# Trial_1_ECE411_Group_15_UPDATED_1.net
KiCad netlist of a schematic drawn in EAGLE
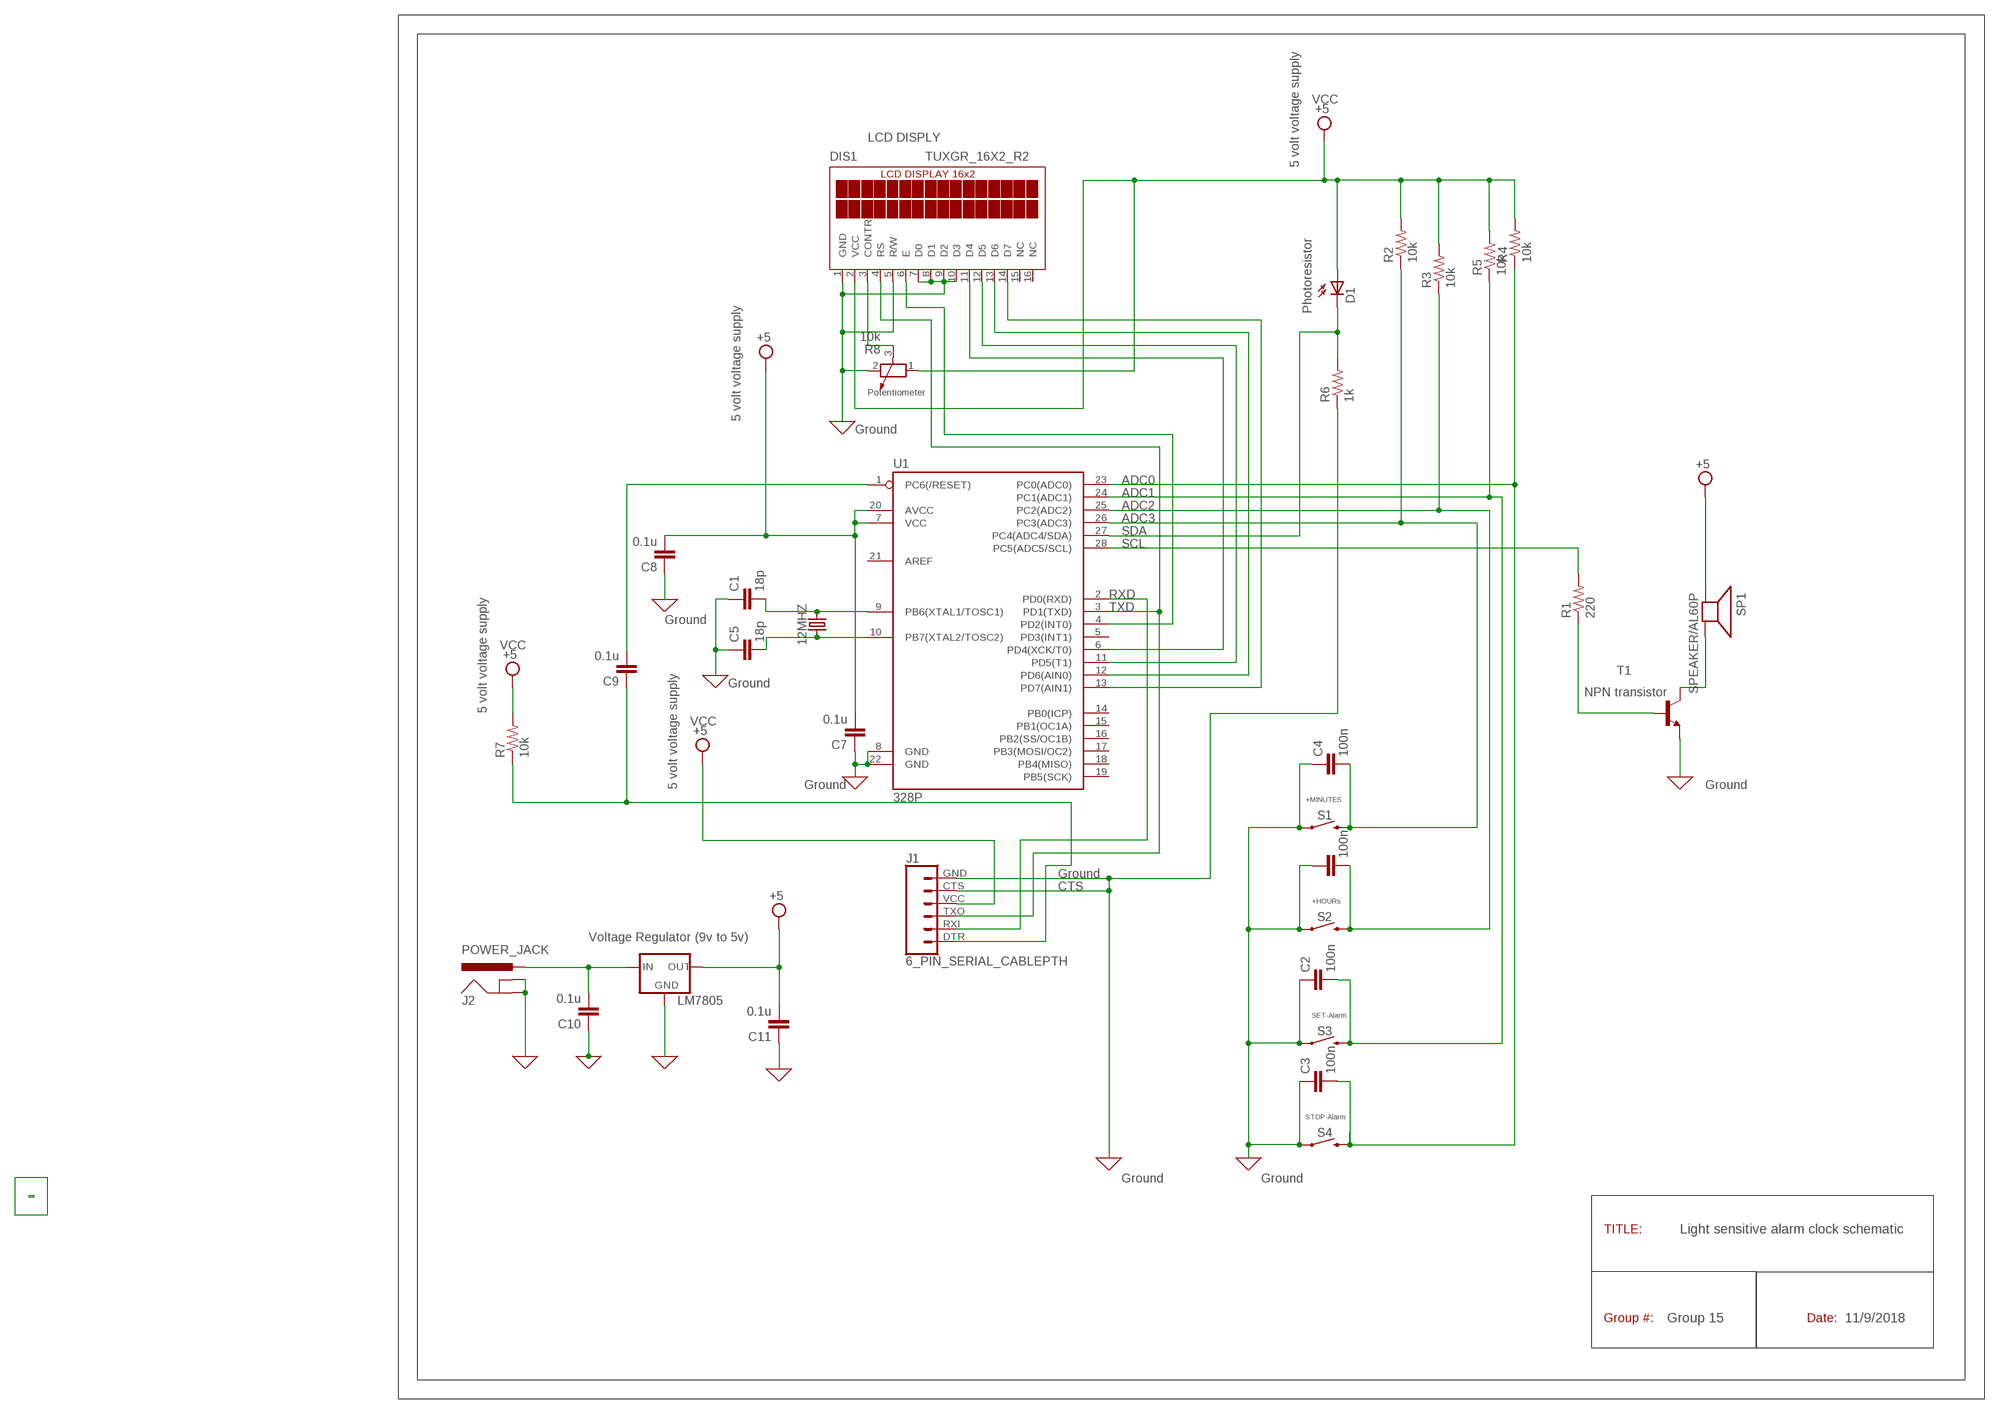
[diagram p0: schematic, sheet 1]

(export (version "E")
  (design (tool "Eeschema 10.0.6"))
  (components
    (comp (ref "12MHZ")
      (value "CRYSTALPTH-2X6")
      (footprint "eagle-import:CRYSTAL-PTH-2X6-CYL")
      (libsource (lib "eagle-import") (part "CRYSTALPTH-2X6"))
    )
    (comp (ref "C1")
      (value "18p")
      (footprint "eagle-import:C2.5-3")
      (libsource (lib "eagle-import") (part "C2,5-3"))
    )
    (comp (ref "C2")
      (value "100n")
      (footprint "eagle-import:C2.5-3")
      (libsource (lib "eagle-import") (part "C2,5-3"))
    )
    (comp (ref "C3")
      (value "100n")
      (footprint "eagle-import:C2.5-3")
      (libsource (lib "eagle-import") (part "C2,5-3"))
    )
    (comp (ref "C4")
      (value "100n")
      (footprint "eagle-import:C2.5-3")
      (libsource (lib "eagle-import") (part "C2,5-3"))
    )
    (comp (ref "C5")
      (value "18p")
      (footprint "eagle-import:C2.5-3")
      (libsource (lib "eagle-import") (part "C2,5-3"))
    )
    (comp (ref "C6")
      (value "100n")
      (footprint "eagle-import:C2.5-3")
      (libsource (lib "eagle-import") (part "C2,5-3"))
    )
    (comp (ref "C7")
      (value "0.1u")
      (footprint "eagle-import:C2.5-3")
      (libsource (lib "eagle-import") (part "C2,5-3"))
    )
    (comp (ref "C8")
      (value "0.1u")
      (footprint "eagle-import:C2.5-3")
      (libsource (lib "eagle-import") (part "C2,5-3"))
    )
    (comp (ref "C9")
      (value "0.1u")
      (footprint "eagle-import:C2.5-3")
      (libsource (lib "eagle-import") (part "C2,5-3"))
    )
    (comp (ref "C10")
      (value "0.1u")
      (footprint "eagle-import:C2.5-3")
      (libsource (lib "eagle-import") (part "C2,5-3"))
    )
    (comp (ref "C11")
      (value "0.1u")
      (footprint "eagle-import:C2.5-3")
      (libsource (lib "eagle-import") (part "C2,5-3"))
    )
    (comp (ref "D1")
      (value "BPW32")
      (footprint "eagle-import:BPW32")
      (libsource (lib "eagle-import") (part "BPW32"))
    )
    (comp (ref "DIS1")
      (value "TUXGR_16X2_R2")
      (footprint "eagle-import:TUXGR_16X2_R2")
      (libsource (lib "eagle-import") (part "TUXGR_16X2_R2"))
    )
    (comp (ref "J1")
      (value "6_PIN_SERIAL_CABLEPTH")
      (footprint "eagle-import:FTDI_BASIC")
      (libsource (lib "eagle-import") (part "6_PIN_SERIAL_CABLEPTH"))
    )
    (comp (ref "J2")
      (value "POWER_JACK")
      (footprint "eagle-import:POWER_JACK_PTH")
      (libsource (lib "eagle-import") (part "POWER_JACK"))
    )
    (comp (ref "LM7805")
      (value "R-78E5.0-1.0")
      (footprint "eagle-import:DC-DC_CONVERTER_78XX")
      (libsource (lib "eagle-import") (part "R-78E5.0-1.0"))
    )
    (comp (ref "R1")
      (value "220")
      (footprint "eagle-import:0204V")
      (libsource (lib "eagle-import") (part "R-US_0204/2V"))
    )
    (comp (ref "R2")
      (value "10k")
      (footprint "eagle-import:0204V")
      (libsource (lib "eagle-import") (part "R-US_0204/2V"))
    )
    (comp (ref "R3")
      (value "10k")
      (footprint "eagle-import:0204V")
      (libsource (lib "eagle-import") (part "R-US_0204/2V"))
    )
    (comp (ref "R4")
      (value "10k")
      (footprint "eagle-import:0204V")
      (libsource (lib "eagle-import") (part "R-US_0204/2V"))
    )
    (comp (ref "R5")
      (value "10k")
      (footprint "eagle-import:0204V")
      (libsource (lib "eagle-import") (part "R-US_0204/2V"))
    )
    (comp (ref "R6")
      (value "1k")
      (footprint "eagle-import:0204V")
      (libsource (lib "eagle-import") (part "R-US_0204/2V"))
    )
    (comp (ref "R7")
      (value "10k")
      (footprint "eagle-import:0204V")
      (libsource (lib "eagle-import") (part "R-US_0204/2V"))
    )
    (comp (ref "R8")
      (value "10k")
      (footprint "eagle-import:PT-10")
      (libsource (lib "eagle-import") (part "POTENTIOMETER_PT-10"))
    )
    (comp (ref "S1")
      (value "MOMENTARY-SWITCH-SPST-PTH-6.0MM")
      (footprint "eagle-import:TACTILE_SWITCH_PTH_6.0MM")
      (libsource (lib "eagle-import") (part "MOMENTARY-SWITCH-SPST-PTH-6.0MM"))
    )
    (comp (ref "S2")
      (value "MOMENTARY-SWITCH-SPST-PTH-6.0MM")
      (footprint "eagle-import:TACTILE_SWITCH_PTH_6.0MM")
      (libsource (lib "eagle-import") (part "MOMENTARY-SWITCH-SPST-PTH-6.0MM"))
    )
    (comp (ref "S3")
      (value "MOMENTARY-SWITCH-SPST-PTH-6.0MM")
      (footprint "eagle-import:TACTILE_SWITCH_PTH_6.0MM")
      (libsource (lib "eagle-import") (part "MOMENTARY-SWITCH-SPST-PTH-6.0MM"))
    )
    (comp (ref "S4")
      (value "MOMENTARY-SWITCH-SPST-PTH-6.0MM")
      (footprint "eagle-import:TACTILE_SWITCH_PTH_6.0MM")
      (libsource (lib "eagle-import") (part "MOMENTARY-SWITCH-SPST-PTH-6.0MM"))
    )
    (comp (ref "SP1")
      (value "SPEAKER/AL60P")
      (footprint "eagle-import:AL60P")
      (libsource (lib "eagle-import") (part "SPEAKER/AL60P"))
    )
    (comp (ref "T1")
      (value "2N2222")
      (footprint "eagle-import:TO92-EBC-OVAL")
      (libsource (lib "eagle-import") (part "2N2222"))
    )
    (comp (ref "U1")
      (value "328P")
      (footprint "eagle-import:DIP28")
      (libsource (lib "eagle-import") (part "ATMEGA328P_PDIP"))
    )
  )
  (nets
    (net (code "1") (name "+5") (class "Default")
      (node (ref "C11") (pin "2") (pinfunction "2_2") (pintype "passive"))
      (node (ref "C7") (pin "2") (pinfunction "2_2") (pintype "passive"))
      (node (ref "C8") (pin "2") (pinfunction "2_2") (pintype "passive"))
      (node (ref "D1") (pin "A") (pinfunction "A_A") (pintype "passive"))
      (node (ref "DIS1") (pin "2") (pinfunction "VCC_2") (pintype "power_in"))
      (node (ref "J1") (pin "VCC") (pinfunction "4_VCC") (pintype "passive"))
      (node (ref "LM7805") (pin "VOUT") (pinfunction "OUT_VOUT") (pintype "passive"))
      (node (ref "R2") (pin "2") (pinfunction "2_2") (pintype "passive"))
      (node (ref "R3") (pin "2") (pinfunction "2_2") (pintype "passive"))
      (node (ref "R4") (pin "2") (pinfunction "2_2") (pintype "passive"))
      (node (ref "R5") (pin "2") (pinfunction "2_2") (pintype "passive"))
      (node (ref "R7") (pin "2") (pinfunction "2_2") (pintype "passive"))
      (node (ref "R8") (pin "1") (pinfunction "1_1") (pintype "passive"))
      (node (ref "SP1") (pin "1") (pinfunction "+_1") (pintype "passive"))
      (node (ref "U1") (pin "20") (pinfunction "AVCC_20") (pintype "bidirectional"))
      (node (ref "U1") (pin "7") (pinfunction "VCC_7") (pintype "bidirectional"))
    )
    (net (code "2") (name "GND") (class "Default")
      (node (ref "C1") (pin "1") (pinfunction "1_1") (pintype "passive"))
      (node (ref "C10") (pin "1") (pinfunction "1_1") (pintype "passive"))
      (node (ref "C11") (pin "1") (pinfunction "1_1") (pintype "passive"))
      (node (ref "C2") (pin "1") (pinfunction "1_1") (pintype "passive"))
      (node (ref "C3") (pin "1") (pinfunction "1_1") (pintype "passive"))
      (node (ref "C4") (pin "1") (pinfunction "1_1") (pintype "passive"))
      (node (ref "C5") (pin "1") (pinfunction "1_1") (pintype "passive"))
      (node (ref "C6") (pin "1") (pinfunction "1_1") (pintype "passive"))
      (node (ref "C7") (pin "1") (pinfunction "1_1") (pintype "passive"))
      (node (ref "C8") (pin "1") (pinfunction "1_1") (pintype "passive"))
      (node (ref "DIS1") (pin "1") (pinfunction "GND_1") (pintype "power_in"))
      (node (ref "DIS1") (pin "10") (pinfunction "D3_10") (pintype "input"))
      (node (ref "DIS1") (pin "5") (pinfunction "R/W_5") (pintype "input"))
      (node (ref "DIS1") (pin "7") (pinfunction "D0_7") (pintype "input"))
      (node (ref "DIS1") (pin "8") (pinfunction "D1_8") (pintype "input"))
      (node (ref "DIS1") (pin "9") (pinfunction "D2_9") (pintype "input"))
      (node (ref "J1") (pin "CTS") (pinfunction "5_CTS") (pintype "passive"))
      (node (ref "J1") (pin "GND") (pinfunction "6_GND") (pintype "passive"))
      (node (ref "J2") (pin "GND") (pinfunction "GND_GND") (pintype "bidirectional"))
      (node (ref "J2") (pin "GNDBREAK") (pinfunction "GNDBREAK_GNDBREAK") (pintype "bidirectional"))
      (node (ref "LM7805") (pin "GND") (pinfunction "GND_GND") (pintype "input"))
      (node (ref "R6") (pin "1") (pinfunction "1_1") (pintype "passive"))
      (node (ref "R8") (pin "2") (pinfunction "2_2") (pintype "passive"))
      (node (ref "S1") (pin "1") (pinfunction "1_1") (pintype "passive"))
      (node (ref "S2") (pin "1") (pinfunction "1_1") (pintype "passive"))
      (node (ref "S3") (pin "1") (pinfunction "1_1") (pintype "passive"))
      (node (ref "S4") (pin "1") (pinfunction "1_1") (pintype "passive"))
      (node (ref "T1") (pin "E") (pinfunction "E_E") (pintype "passive"))
      (node (ref "U1") (pin "22") (pinfunction "GND_22") (pintype "bidirectional"))
      (node (ref "U1") (pin "8") (pinfunction "GND_8") (pintype "bidirectional"))
    )
    (net (code "3") (name "Net-(D1-C)") (class "Default")
      (node (ref "D1") (pin "K") (pinfunction "C_K") (pintype "passive"))
      (node (ref "R6") (pin "2") (pinfunction "2_2") (pintype "passive"))
      (node (ref "U1") (pin "27") (pinfunction "PC4(ADC4/SDA)_27") (pintype "bidirectional"))
    )
    (net (code "4") (name "Net-(DIS1-CONTR)") (class "Default")
      (node (ref "DIS1") (pin "3") (pinfunction "CONTR_3") (pintype "input"))
      (node (ref "R8") (pin "3") (pinfunction "3_3") (pintype "passive"))
    )
    (net (code "5") (name "Net-(DIS1-D4)") (class "Default")
      (node (ref "DIS1") (pin "11") (pinfunction "D4_11") (pintype "input"))
      (node (ref "U1") (pin "6") (pinfunction "PD4(XCK/T0)_6") (pintype "bidirectional"))
    )
    (net (code "6") (name "Net-(DIS1-D5)") (class "Default")
      (node (ref "DIS1") (pin "12") (pinfunction "D5_12") (pintype "input"))
      (node (ref "U1") (pin "11") (pinfunction "PD5(T1)_11") (pintype "bidirectional"))
    )
    (net (code "7") (name "Net-(DIS1-D6)") (class "Default")
      (node (ref "DIS1") (pin "13") (pinfunction "D6_13") (pintype "input"))
      (node (ref "U1") (pin "12") (pinfunction "PD6(AIN0)_12") (pintype "bidirectional"))
    )
    (net (code "8") (name "Net-(DIS1-D7)") (class "Default")
      (node (ref "DIS1") (pin "14") (pinfunction "D7_14") (pintype "input"))
      (node (ref "U1") (pin "13") (pinfunction "PD7(AIN1)_13") (pintype "bidirectional"))
    )
    (net (code "9") (name "Net-(DIS1-E)") (class "Default")
      (node (ref "DIS1") (pin "6") (pinfunction "E_6") (pintype "input"))
      (node (ref "U1") (pin "4") (pinfunction "PD2(INT0)_4") (pintype "bidirectional"))
    )
    (net (code "10") (name "Net-(DIS1-RS)") (class "Default")
      (node (ref "DIS1") (pin "4") (pinfunction "RS_4") (pintype "input"))
      (node (ref "J1") (pin "TXO") (pinfunction "3_TXO") (pintype "passive"))
      (node (ref "U1") (pin "3") (pinfunction "PD1(TXD)_3") (pintype "bidirectional"))
    )
    (net (code "11") (name "Net-(J1-1)") (class "Default")
      (node (ref "C9") (pin "1") (pinfunction "1_1") (pintype "passive"))
      (node (ref "J1") (pin "DTR") (pinfunction "1_DTR") (pintype "passive"))
      (node (ref "R7") (pin "1") (pinfunction "1_1") (pintype "passive"))
    )
    (net (code "12") (name "Net-(J1-2)") (class "Default")
      (node (ref "J1") (pin "RXI") (pinfunction "2_RXI") (pintype "passive"))
      (node (ref "U1") (pin "2") (pinfunction "PD0(RXD)_2") (pintype "bidirectional"))
    )
    (net (code "13") (name "Net-(LM7805-IN)") (class "Default")
      (node (ref "C10") (pin "2") (pinfunction "2_2") (pintype "passive"))
      (node (ref "J2") (pin "PWR") (pinfunction "PWR_PWR") (pintype "bidirectional"))
      (node (ref "LM7805") (pin "VIN") (pinfunction "IN_VIN") (pintype "input"))
    )
    (net (code "14") (name "Net-(R1-Pad1)") (class "Default")
      (node (ref "R1") (pin "1") (pinfunction "1_1") (pintype "passive"))
      (node (ref "T1") (pin "B") (pinfunction "B_B") (pintype "passive"))
    )
    (net (code "15") (name "Net-(S1-2)") (class "Default")
      (node (ref "C4") (pin "2") (pinfunction "2_2") (pintype "passive"))
      (node (ref "R2") (pin "1") (pinfunction "1_1") (pintype "passive"))
      (node (ref "S1") (pin "3") (pinfunction "2_3") (pintype "passive"))
      (node (ref "U1") (pin "26") (pinfunction "PC3(ADC3)_26") (pintype "bidirectional"))
    )
    (net (code "16") (name "Net-(S2-2)") (class "Default")
      (node (ref "C6") (pin "2") (pinfunction "2_2") (pintype "passive"))
      (node (ref "R3") (pin "1") (pinfunction "1_1") (pintype "passive"))
      (node (ref "S2") (pin "3") (pinfunction "2_3") (pintype "passive"))
      (node (ref "U1") (pin "25") (pinfunction "PC2(ADC2)_25") (pintype "bidirectional"))
    )
    (net (code "17") (name "Net-(S3-2)") (class "Default")
      (node (ref "C2") (pin "2") (pinfunction "2_2") (pintype "passive"))
      (node (ref "R5") (pin "1") (pinfunction "1_1") (pintype "passive"))
      (node (ref "S3") (pin "3") (pinfunction "2_3") (pintype "passive"))
      (node (ref "U1") (pin "24") (pinfunction "PC1(ADC1)_24") (pintype "bidirectional"))
    )
    (net (code "18") (name "Net-(S4-2)") (class "Default")
      (node (ref "C3") (pin "2") (pinfunction "2_2") (pintype "passive"))
      (node (ref "R4") (pin "1") (pinfunction "1_1") (pintype "passive"))
      (node (ref "S4") (pin "3") (pinfunction "2_3") (pintype "passive"))
      (node (ref "U1") (pin "23") (pinfunction "PC0(ADC0)_23") (pintype "bidirectional"))
    )
    (net (code "19") (name "Net-(SP1--)") (class "Default")
      (node (ref "SP1") (pin "2") (pinfunction "-_2") (pintype "passive"))
      (node (ref "T1") (pin "C") (pinfunction "C_C") (pintype "passive"))
    )
    (net (code "20") (name "Net-(U1-PB6(XTAL1{slash}TOSC1))") (class "Default")
      (node (ref "12MHZ") (pin "2") (pinfunction "2_2") (pintype "passive"))
      (node (ref "C1") (pin "2") (pinfunction "2_2") (pintype "passive"))
      (node (ref "U1") (pin "9") (pinfunction "PB6(XTAL1/TOSC1)_9") (pintype "bidirectional"))
    )
    (net (code "21") (name "Net-(U1-PB7(XTAL2{slash}TOSC2))") (class "Default")
      (node (ref "12MHZ") (pin "1") (pinfunction "1_1") (pintype "passive"))
      (node (ref "C5") (pin "2") (pinfunction "2_2") (pintype "passive"))
      (node (ref "U1") (pin "10") (pinfunction "PB7(XTAL2/TOSC2)_10") (pintype "bidirectional"))
    )
    (net (code "22") (name "Net-(U1-PC5(ADC5{slash}SCL))") (class "Default")
      (node (ref "R1") (pin "2") (pinfunction "2_2") (pintype "passive"))
      (node (ref "U1") (pin "28") (pinfunction "PC5(ADC5/SCL)_28") (pintype "bidirectional"))
    )
    (net (code "23") (name "Net-(U1-PC6({slash}RESET))") (class "Default")
      (node (ref "C9") (pin "2") (pinfunction "2_2") (pintype "passive"))
      (node (ref "U1") (pin "1") (pinfunction "PC6(/RESET)_1") (pintype "bidirectional"))
    )
    (net (code "24") (name "unconnected-(DIS1-NC-Pad15)") (class "Default")
      (node (ref "DIS1") (pin "15") (pinfunction "NC_15") (pintype "no_connect"))
    )
    (net (code "25") (name "unconnected-(DIS1-NC-Pad16)") (class "Default")
      (node (ref "DIS1") (pin "16") (pinfunction "NC_16") (pintype "no_connect"))
    )
    (net (code "26") (name "unconnected-(U1-AREF-Pad21)") (class "Default")
      (node (ref "U1") (pin "21") (pinfunction "AREF_21") (pintype "bidirectional"))
    )
    (net (code "27") (name "unconnected-(U1-PB0(ICP)-Pad14)") (class "Default")
      (node (ref "U1") (pin "14") (pinfunction "PB0(ICP)_14") (pintype "bidirectional"))
    )
    (net (code "28") (name "unconnected-(U1-PB1(OC1A)-Pad15)") (class "Default")
      (node (ref "U1") (pin "15") (pinfunction "PB1(OC1A)_15") (pintype "bidirectional"))
    )
    (net (code "29") (name "unconnected-(U1-PB2(SS{slash}OC1B)-Pad16)") (class "Default")
      (node (ref "U1") (pin "16") (pinfunction "PB2(SS/OC1B)_16") (pintype "bidirectional"))
    )
    (net (code "30") (name "unconnected-(U1-PB3(MOSI{slash}OC2)-Pad17)") (class "Default")
      (node (ref "U1") (pin "17") (pinfunction "PB3(MOSI/OC2)_17") (pintype "bidirectional"))
    )
    (net (code "31") (name "unconnected-(U1-PB4(MISO)-Pad18)") (class "Default")
      (node (ref "U1") (pin "18") (pinfunction "PB4(MISO)_18") (pintype "bidirectional"))
    )
    (net (code "32") (name "unconnected-(U1-PB5(SCK)-Pad19)") (class "Default")
      (node (ref "U1") (pin "19") (pinfunction "PB5(SCK)_19") (pintype "bidirectional"))
    )
    (net (code "33") (name "unconnected-(U1-PD3(INT1)-Pad5)") (class "Default")
      (node (ref "U1") (pin "5") (pinfunction "PD3(INT1)_5") (pintype "bidirectional"))
    )
  )
)
